# vfd_controller_cpu.net
KiCad netlist of a schematic drawn in EAGLE
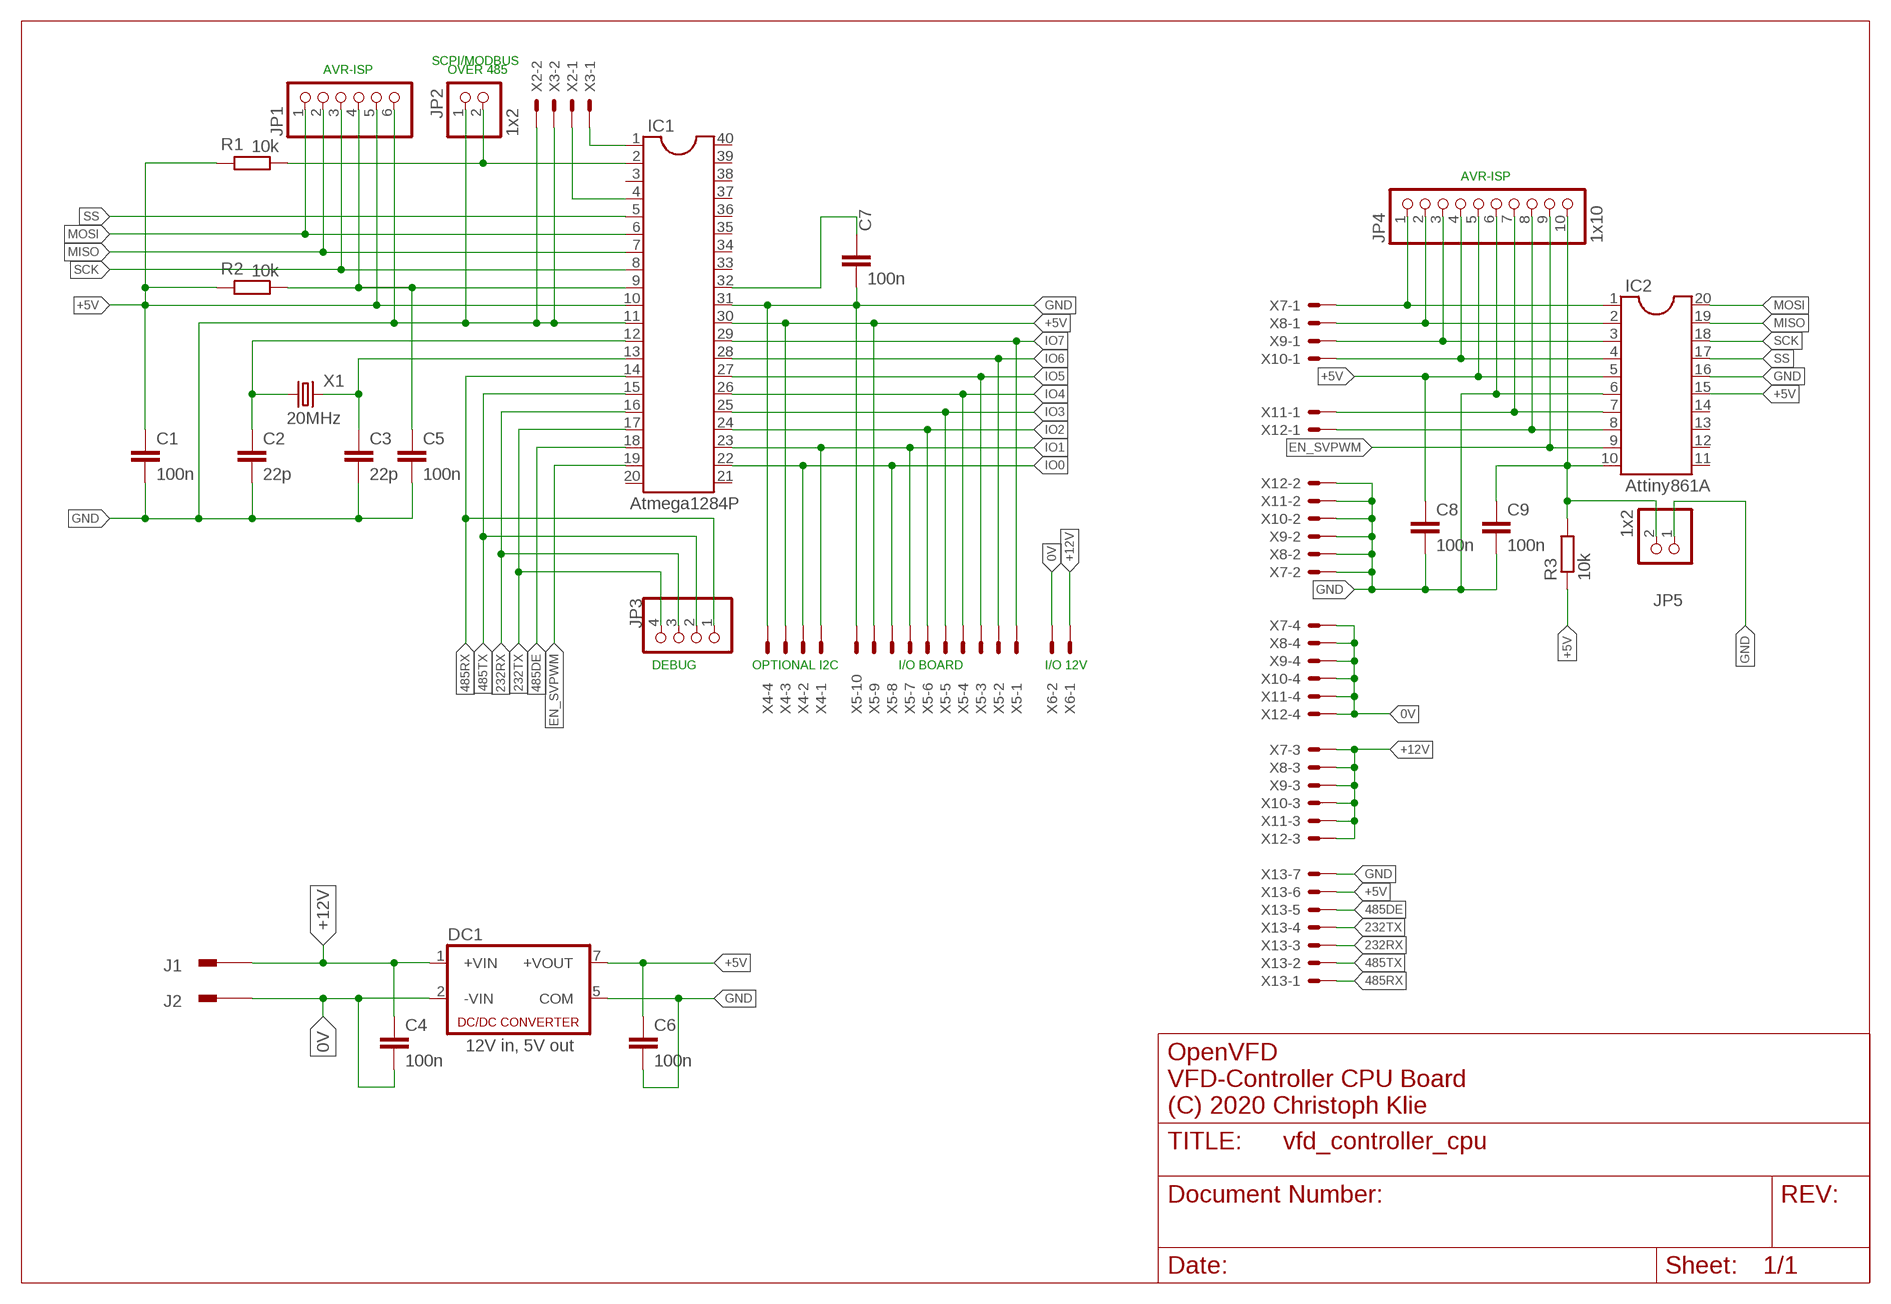
[diagram p0: schematic, sheet 1]

(export (version "E")
  (design (tool "Eeschema 10.0.6"))
  (components
    (comp (ref "C1")
      (value "100n")
      (footprint "eagle-import:C025-024X044")
      (libsource (lib "eagle-import") (part "C-EU025-024X044"))
    )
    (comp (ref "C2")
      (value "22p")
      (footprint "eagle-import:C025-024X044")
      (libsource (lib "eagle-import") (part "C-EU025-024X044"))
    )
    (comp (ref "C3")
      (value "22p")
      (footprint "eagle-import:C025-024X044")
      (libsource (lib "eagle-import") (part "C-EU025-024X044"))
    )
    (comp (ref "C4")
      (value "100n")
      (footprint "eagle-import:C025-024X044")
      (libsource (lib "eagle-import") (part "C-EU025-024X044"))
    )
    (comp (ref "C5")
      (value "100n")
      (footprint "eagle-import:C050-025X075")
      (libsource (lib "eagle-import") (part "C-EU050-025X075"))
    )
    (comp (ref "C6")
      (value "100n")
      (footprint "eagle-import:C050-025X075")
      (libsource (lib "eagle-import") (part "C-EU050-025X075"))
    )
    (comp (ref "C7")
      (value "100n")
      (footprint "eagle-import:C025-024X044")
      (libsource (lib "eagle-import") (part "C-EU025-024X044"))
    )
    (comp (ref "C8")
      (value "100n")
      (footprint "eagle-import:C025-024X044")
      (libsource (lib "eagle-import") (part "C-EU025-024X044"))
    )
    (comp (ref "C9")
      (value "100n")
      (footprint "eagle-import:C025-024X044")
      (libsource (lib "eagle-import") (part "C-EU025-024X044"))
    )
    (comp (ref "DC1")
      (value "12V in, 5V out")
      (footprint "eagle-import:MEV")
      (libsource (lib "eagle-import") (part "MEV"))
    )
    (comp (ref "IC1")
      (value "Atmega1284P")
      (footprint "eagle-import:DIL40")
      (libsource (lib "eagle-import") (part "DIL40"))
    )
    (comp (ref "IC2")
      (value "Attiny861A")
      (footprint "eagle-import:DIL20")
      (libsource (lib "eagle-import") (part "DIL20"))
    )
    (comp (ref "J1")
      (value "PIN2F061.200")
      (footprint "eagle-import:F061.200")
      (libsource (lib "eagle-import") (part "PIN2F061.200"))
    )
    (comp (ref "J2")
      (value "PIN2F061.200")
      (footprint "eagle-import:F061.200")
      (libsource (lib "eagle-import") (part "PIN2F061.200"))
    )
    (comp (ref "JP1")
      (value "1x6")
      (footprint "eagle-import:1X06")
      (libsource (lib "eagle-import") (part "PINHD-1X6"))
    )
    (comp (ref "JP2")
      (value "1x2")
      (footprint "eagle-import:1X02")
      (libsource (lib "eagle-import") (part "PINHD-1X2"))
    )
    (comp (ref "JP3")
      (value "1x4")
      (footprint "eagle-import:1X04")
      (libsource (lib "eagle-import") (part "PINHD-1X4"))
    )
    (comp (ref "JP4")
      (value "1x10")
      (footprint "eagle-import:1X10")
      (libsource (lib "eagle-import") (part "PINHD-1X10"))
    )
    (comp (ref "JP5")
      (value "1x2")
      (footprint "eagle-import:1X02")
      (libsource (lib "eagle-import") (part "PINHD-1X2"))
    )
    (comp (ref "R1")
      (value "10k")
      (footprint "eagle-import:0207_12")
      (libsource (lib "eagle-import") (part "R-EU_0207/12"))
    )
    (comp (ref "R2")
      (value "10k")
      (footprint "eagle-import:0204V")
      (libsource (lib "eagle-import") (part "R-EU_0204/2V"))
    )
    (comp (ref "R3")
      (value "10k")
      (footprint "eagle-import:0207_12")
      (libsource (lib "eagle-import") (part "R-EU_0207/12"))
    )
    (comp (ref "X1")
      (value "20MHz")
      (footprint "eagle-import:HC49")
      (libsource (lib "eagle-import") (part "CRYSTALS-NOGND-HC49"))
    )
    (comp (ref "X2")
      (value "JST-XH-02-PIN-LONG-PAD")
      (footprint "eagle-import:JST-XH-02-PACKAGE-LONG-PAD")
      (fields (field (name "R") "JST XH2P ST"))
      (libsource (lib "eagle-import") (part "JST-XH-02-PIN-LONG-PAD"))
    )
    (comp (ref "X3")
      (value "JST-XH-02-PIN-LONG-PAD")
      (footprint "eagle-import:JST-XH-02-PACKAGE-LONG-PAD")
      (fields (field (name "R") "JST XH2P ST"))
      (libsource (lib "eagle-import") (part "JST-XH-02-PIN-LONG-PAD"))
    )
    (comp (ref "X4")
      (value "JST-XH-04-PIN-LONG-PAD")
      (footprint "eagle-import:JST-XH-04-PACKAGE-LONG-PAD")
      (fields (field (name "R") "JST XH4P ST"))
      (libsource (lib "eagle-import") (part "JST-XH-04-PIN-LONG-PAD"))
    )
    (comp (ref "X5")
      (value "JST-XH-10-PIN-LONG-PAD")
      (footprint "eagle-import:JST-XH-10-PACKAGE-LONG-PAD")
      (fields (field (name "R") "JST XH10P ST"))
      (libsource (lib "eagle-import") (part "JST-XH-10-PIN-LONG-PAD"))
    )
    (comp (ref "X6")
      (value "JST-XH-02-PIN-LONG-PAD")
      (footprint "eagle-import:JST-XH-02-PACKAGE-LONG-PAD")
      (fields (field (name "R") "JST XH2P ST"))
      (libsource (lib "eagle-import") (part "JST-XH-02-PIN-LONG-PAD"))
    )
    (comp (ref "X7")
      (value "JST-XH-04-PIN-LONG-PAD")
      (footprint "eagle-import:JST-XH-04-PACKAGE-LONG-PAD")
      (fields (field (name "R") "JST XH4P ST"))
      (libsource (lib "eagle-import") (part "JST-XH-04-PIN-LONG-PAD"))
    )
    (comp (ref "X8")
      (value "JST-XH-04-PIN-LONG-PAD")
      (footprint "eagle-import:JST-XH-04-PACKAGE-LONG-PAD")
      (fields (field (name "R") "JST XH4P ST"))
      (libsource (lib "eagle-import") (part "JST-XH-04-PIN-LONG-PAD"))
    )
    (comp (ref "X9")
      (value "JST-XH-04-PIN-LONG-PAD")
      (footprint "eagle-import:JST-XH-04-PACKAGE-LONG-PAD")
      (fields (field (name "R") "JST XH4P ST"))
      (libsource (lib "eagle-import") (part "JST-XH-04-PIN-LONG-PAD"))
    )
    (comp (ref "X10")
      (value "JST-XH-04-PIN-LONG-PAD")
      (footprint "eagle-import:JST-XH-04-PACKAGE-LONG-PAD")
      (fields (field (name "R") "JST XH4P ST"))
      (libsource (lib "eagle-import") (part "JST-XH-04-PIN-LONG-PAD"))
    )
    (comp (ref "X11")
      (value "JST-XH-04-PIN-LONG-PAD")
      (footprint "eagle-import:JST-XH-04-PACKAGE-LONG-PAD")
      (fields (field (name "R") "JST XH4P ST"))
      (libsource (lib "eagle-import") (part "JST-XH-04-PIN-LONG-PAD"))
    )
    (comp (ref "X12")
      (value "JST-XH-04-PIN-LONG-PAD")
      (footprint "eagle-import:JST-XH-04-PACKAGE-LONG-PAD")
      (fields (field (name "R") "JST XH4P ST"))
      (libsource (lib "eagle-import") (part "JST-XH-04-PIN-LONG-PAD"))
    )
    (comp (ref "X13")
      (value "JST-XH-07-PIN-LONG-PAD")
      (footprint "eagle-import:JST-XH-07-PACKAGE-LONG-PAD")
      (fields (field (name "R") "JST XH7P ST"))
      (libsource (lib "eagle-import") (part "JST-XH-07-PIN-LONG-PAD"))
    )
  )
  (nets
    (net (code "1") (name "+5V") (class "Default")
      (node (ref "C1") (pin "1") (pinfunction "1_1") (pintype "passive"))
      (node (ref "C6") (pin "1") (pinfunction "1_1") (pintype "passive"))
      (node (ref "C8") (pin "1") (pinfunction "1_1") (pintype "passive"))
      (node (ref "DC1") (pin "7") (pinfunction "+VOUT_7") (pintype "passive"))
      (node (ref "IC1") (pin "10") (pinfunction "10_10") (pintype "passive"))
      (node (ref "IC1") (pin "30") (pinfunction "30_30") (pintype "passive"))
      (node (ref "IC2") (pin "15") (pinfunction "15_15") (pintype "passive"))
      (node (ref "IC2") (pin "5") (pinfunction "5_5") (pintype "passive"))
      (node (ref "JP1") (pin "5") (pinfunction "5_5") (pintype "passive"))
      (node (ref "JP4") (pin "5") (pinfunction "5_5") (pintype "passive"))
      (node (ref "R1") (pin "2") (pinfunction "2_2") (pintype "passive"))
      (node (ref "R2") (pin "2") (pinfunction "2_2") (pintype "passive"))
      (node (ref "R3") (pin "1") (pinfunction "1_1") (pintype "passive"))
      (node (ref "X13") (pin "6") (pinfunction "S_6") (pintype "passive"))
      (node (ref "X4") (pin "3") (pinfunction "S_3") (pintype "passive"))
      (node (ref "X5") (pin "9") (pinfunction "S_9") (pintype "passive"))
    )
    (net (code "2") (name "+12V") (class "Default")
      (node (ref "C4") (pin "1") (pinfunction "1_1") (pintype "passive"))
      (node (ref "DC1") (pin "1") (pinfunction "+VIN_1") (pintype "passive"))
      (node (ref "J1") (pin "1A") (pinfunction "1_1A") (pintype "passive"))
      (node (ref "J1") (pin "1B") (pinfunction "1_1B") (pintype "passive"))
      (node (ref "X10") (pin "3") (pinfunction "S_3") (pintype "passive"))
      (node (ref "X11") (pin "3") (pinfunction "S_3") (pintype "passive"))
      (node (ref "X12") (pin "3") (pinfunction "S_3") (pintype "passive"))
      (node (ref "X6") (pin "1") (pinfunction "S_1") (pintype "passive"))
      (node (ref "X7") (pin "3") (pinfunction "S_3") (pintype "passive"))
      (node (ref "X8") (pin "3") (pinfunction "S_3") (pintype "passive"))
      (node (ref "X9") (pin "3") (pinfunction "S_3") (pintype "passive"))
    )
    (net (code "3") (name "0V") (class "Default")
      (node (ref "C4") (pin "2") (pinfunction "2_2") (pintype "passive"))
      (node (ref "DC1") (pin "2") (pinfunction "-VIN_2") (pintype "passive"))
      (node (ref "J2") (pin "1A") (pinfunction "1_1A") (pintype "passive"))
      (node (ref "J2") (pin "1B") (pinfunction "1_1B") (pintype "passive"))
      (node (ref "X10") (pin "4") (pinfunction "S_4") (pintype "passive"))
      (node (ref "X11") (pin "4") (pinfunction "S_4") (pintype "passive"))
      (node (ref "X12") (pin "4") (pinfunction "S_4") (pintype "passive"))
      (node (ref "X6") (pin "2") (pinfunction "S_2") (pintype "passive"))
      (node (ref "X7") (pin "4") (pinfunction "S_4") (pintype "passive"))
      (node (ref "X8") (pin "4") (pinfunction "S_4") (pintype "passive"))
      (node (ref "X9") (pin "4") (pinfunction "S_4") (pintype "passive"))
    )
    (net (code "4") (name "232RX") (class "Default")
      (node (ref "IC1") (pin "16") (pinfunction "16_16") (pintype "passive"))
      (node (ref "JP3") (pin "3") (pinfunction "3_3") (pintype "passive"))
      (node (ref "X13") (pin "3") (pinfunction "S_3") (pintype "passive"))
    )
    (net (code "5") (name "232TX") (class "Default")
      (node (ref "IC1") (pin "17") (pinfunction "17_17") (pintype "passive"))
      (node (ref "JP3") (pin "4") (pinfunction "4_4") (pintype "passive"))
      (node (ref "X13") (pin "4") (pinfunction "S_4") (pintype "passive"))
    )
    (net (code "6") (name "485DE") (class "Default")
      (node (ref "IC1") (pin "18") (pinfunction "18_18") (pintype "passive"))
      (node (ref "X13") (pin "5") (pinfunction "S_5") (pintype "passive"))
    )
    (net (code "7") (name "485RX") (class "Default")
      (node (ref "IC1") (pin "14") (pinfunction "14_14") (pintype "passive"))
      (node (ref "JP3") (pin "1") (pinfunction "1_1") (pintype "passive"))
      (node (ref "X13") (pin "1") (pinfunction "S_1") (pintype "passive"))
    )
    (net (code "8") (name "485TX") (class "Default")
      (node (ref "IC1") (pin "15") (pinfunction "15_15") (pintype "passive"))
      (node (ref "JP3") (pin "2") (pinfunction "2_2") (pintype "passive"))
      (node (ref "X13") (pin "2") (pinfunction "S_2") (pintype "passive"))
    )
    (net (code "9") (name "EN_SVPWM") (class "Default")
      (node (ref "IC1") (pin "19") (pinfunction "19_19") (pintype "passive"))
      (node (ref "IC2") (pin "9") (pinfunction "9_9") (pintype "passive"))
      (node (ref "JP4") (pin "9") (pinfunction "9_9") (pintype "passive"))
    )
    (net (code "10") (name "GND") (class "Default")
      (node (ref "C1") (pin "2") (pinfunction "2_2") (pintype "passive"))
      (node (ref "C2") (pin "2") (pinfunction "2_2") (pintype "passive"))
      (node (ref "C3") (pin "2") (pinfunction "2_2") (pintype "passive"))
      (node (ref "C5") (pin "2") (pinfunction "2_2") (pintype "passive"))
      (node (ref "C6") (pin "2") (pinfunction "2_2") (pintype "passive"))
      (node (ref "C7") (pin "2") (pinfunction "2_2") (pintype "passive"))
      (node (ref "C8") (pin "2") (pinfunction "2_2") (pintype "passive"))
      (node (ref "C9") (pin "2") (pinfunction "2_2") (pintype "passive"))
      (node (ref "DC1") (pin "5") (pinfunction "COM_5") (pintype "passive"))
      (node (ref "IC1") (pin "11") (pinfunction "11_11") (pintype "passive"))
      (node (ref "IC1") (pin "31") (pinfunction "31_31") (pintype "passive"))
      (node (ref "IC2") (pin "16") (pinfunction "16_16") (pintype "passive"))
      (node (ref "IC2") (pin "6") (pinfunction "6_6") (pintype "passive"))
      (node (ref "JP1") (pin "6") (pinfunction "6_6") (pintype "passive"))
      (node (ref "JP2") (pin "1") (pinfunction "1_1") (pintype "passive"))
      (node (ref "JP4") (pin "6") (pinfunction "6_6") (pintype "passive"))
      (node (ref "JP5") (pin "1") (pinfunction "1_1") (pintype "passive"))
      (node (ref "X10") (pin "2") (pinfunction "S_2") (pintype "passive"))
      (node (ref "X11") (pin "2") (pinfunction "S_2") (pintype "passive"))
      (node (ref "X12") (pin "2") (pinfunction "S_2") (pintype "passive"))
      (node (ref "X13") (pin "7") (pinfunction "S_7") (pintype "passive"))
      (node (ref "X2") (pin "2") (pinfunction "S_2") (pintype "passive"))
      (node (ref "X3") (pin "2") (pinfunction "S_2") (pintype "passive"))
      (node (ref "X4") (pin "4") (pinfunction "S_4") (pintype "passive"))
      (node (ref "X5") (pin "10") (pinfunction "S_10") (pintype "passive"))
      (node (ref "X7") (pin "2") (pinfunction "S_2") (pintype "passive"))
      (node (ref "X8") (pin "2") (pinfunction "S_2") (pintype "passive"))
      (node (ref "X9") (pin "2") (pinfunction "S_2") (pintype "passive"))
    )
    (net (code "11") (name "IO0") (class "Default")
      (node (ref "IC1") (pin "22") (pinfunction "22_22") (pintype "passive"))
      (node (ref "X4") (pin "2") (pinfunction "S_2") (pintype "passive"))
      (node (ref "X5") (pin "8") (pinfunction "S_8") (pintype "passive"))
    )
    (net (code "12") (name "IO1") (class "Default")
      (node (ref "IC1") (pin "23") (pinfunction "23_23") (pintype "passive"))
      (node (ref "X4") (pin "1") (pinfunction "S_1") (pintype "passive"))
      (node (ref "X5") (pin "7") (pinfunction "S_7") (pintype "passive"))
    )
    (net (code "13") (name "IO2") (class "Default")
      (node (ref "IC1") (pin "24") (pinfunction "24_24") (pintype "passive"))
      (node (ref "X5") (pin "6") (pinfunction "S_6") (pintype "passive"))
    )
    (net (code "14") (name "IO3") (class "Default")
      (node (ref "IC1") (pin "25") (pinfunction "25_25") (pintype "passive"))
      (node (ref "X5") (pin "5") (pinfunction "S_5") (pintype "passive"))
    )
    (net (code "15") (name "IO4") (class "Default")
      (node (ref "IC1") (pin "26") (pinfunction "26_26") (pintype "passive"))
      (node (ref "X5") (pin "4") (pinfunction "S_4") (pintype "passive"))
    )
    (net (code "16") (name "IO5") (class "Default")
      (node (ref "IC1") (pin "27") (pinfunction "27_27") (pintype "passive"))
      (node (ref "X5") (pin "3") (pinfunction "S_3") (pintype "passive"))
    )
    (net (code "17") (name "IO6") (class "Default")
      (node (ref "IC1") (pin "28") (pinfunction "28_28") (pintype "passive"))
      (node (ref "X5") (pin "2") (pinfunction "S_2") (pintype "passive"))
    )
    (net (code "18") (name "IO7") (class "Default")
      (node (ref "IC1") (pin "29") (pinfunction "29_29") (pintype "passive"))
      (node (ref "X5") (pin "1") (pinfunction "S_1") (pintype "passive"))
    )
    (net (code "19") (name "MISO") (class "Default")
      (node (ref "IC1") (pin "7") (pinfunction "7_7") (pintype "passive"))
      (node (ref "IC2") (pin "19") (pinfunction "19_19") (pintype "passive"))
      (node (ref "JP1") (pin "2") (pinfunction "2_2") (pintype "passive"))
    )
    (net (code "20") (name "MOSI") (class "Default")
      (node (ref "IC1") (pin "6") (pinfunction "6_6") (pintype "passive"))
      (node (ref "IC2") (pin "20") (pinfunction "20_20") (pintype "passive"))
      (node (ref "JP1") (pin "1") (pinfunction "1_1") (pintype "passive"))
    )
    (net (code "21") (name "Net-(C2-Pad1)") (class "Default")
      (node (ref "C2") (pin "1") (pinfunction "1_1") (pintype "passive"))
      (node (ref "IC1") (pin "12") (pinfunction "12_12") (pintype "passive"))
      (node (ref "X1") (pin "1") (pinfunction "1_1") (pintype "passive"))
    )
    (net (code "22") (name "Net-(C3-Pad1)") (class "Default")
      (node (ref "C3") (pin "1") (pinfunction "1_1") (pintype "passive"))
      (node (ref "IC1") (pin "13") (pinfunction "13_13") (pintype "passive"))
      (node (ref "X1") (pin "2") (pinfunction "2_2") (pintype "passive"))
    )
    (net (code "23") (name "Net-(C5-Pad1)") (class "Default")
      (node (ref "C5") (pin "1") (pinfunction "1_1") (pintype "passive"))
      (node (ref "IC1") (pin "9") (pinfunction "9_9") (pintype "passive"))
      (node (ref "JP1") (pin "4") (pinfunction "4_4") (pintype "passive"))
      (node (ref "R2") (pin "1") (pinfunction "1_1") (pintype "passive"))
    )
    (net (code "24") (name "Net-(C7-Pad1)") (class "Default")
      (node (ref "C7") (pin "1") (pinfunction "1_1") (pintype "passive"))
      (node (ref "IC1") (pin "32") (pinfunction "32_32") (pintype "passive"))
    )
    (net (code "25") (name "Net-(C9-Pad1)") (class "Default")
      (node (ref "C9") (pin "1") (pinfunction "1_1") (pintype "passive"))
      (node (ref "IC2") (pin "10") (pinfunction "10_10") (pintype "passive"))
      (node (ref "JP4") (pin "10") (pinfunction "10_10") (pintype "passive"))
      (node (ref "JP5") (pin "2") (pinfunction "2_2") (pintype "passive"))
      (node (ref "R3") (pin "2") (pinfunction "2_2") (pintype "passive"))
    )
    (net (code "26") (name "Net-(IC1-Pad2)") (class "Default")
      (node (ref "IC1") (pin "2") (pinfunction "2_2") (pintype "passive"))
      (node (ref "JP2") (pin "2") (pinfunction "2_2") (pintype "passive"))
      (node (ref "R1") (pin "1") (pinfunction "1_1") (pintype "passive"))
    )
    (net (code "27") (name "Net-(X2A-S)") (class "Default")
      (node (ref "IC1") (pin "4") (pinfunction "4_4") (pintype "passive"))
      (node (ref "X2") (pin "1") (pinfunction "S_1") (pintype "passive"))
    )
    (net (code "28") (name "Net-(X3A-S)") (class "Default")
      (node (ref "IC1") (pin "1") (pinfunction "1_1") (pintype "passive"))
      (node (ref "X3") (pin "1") (pinfunction "S_1") (pintype "passive"))
    )
    (net (code "29") (name "Net-(X7A-S)") (class "Default")
      (node (ref "IC2") (pin "1") (pinfunction "1_1") (pintype "passive"))
      (node (ref "JP4") (pin "1") (pinfunction "1_1") (pintype "passive"))
      (node (ref "X7") (pin "1") (pinfunction "S_1") (pintype "passive"))
    )
    (net (code "30") (name "Net-(X8A-S)") (class "Default")
      (node (ref "IC2") (pin "2") (pinfunction "2_2") (pintype "passive"))
      (node (ref "JP4") (pin "2") (pinfunction "2_2") (pintype "passive"))
      (node (ref "X8") (pin "1") (pinfunction "S_1") (pintype "passive"))
    )
    (net (code "31") (name "Net-(X9A-S)") (class "Default")
      (node (ref "IC2") (pin "3") (pinfunction "3_3") (pintype "passive"))
      (node (ref "JP4") (pin "3") (pinfunction "3_3") (pintype "passive"))
      (node (ref "X9") (pin "1") (pinfunction "S_1") (pintype "passive"))
    )
    (net (code "32") (name "Net-(X10A-S)") (class "Default")
      (node (ref "IC2") (pin "4") (pinfunction "4_4") (pintype "passive"))
      (node (ref "JP4") (pin "4") (pinfunction "4_4") (pintype "passive"))
      (node (ref "X10") (pin "1") (pinfunction "S_1") (pintype "passive"))
    )
    (net (code "33") (name "Net-(X11A-S)") (class "Default")
      (node (ref "IC2") (pin "7") (pinfunction "7_7") (pintype "passive"))
      (node (ref "JP4") (pin "7") (pinfunction "7_7") (pintype "passive"))
      (node (ref "X11") (pin "1") (pinfunction "S_1") (pintype "passive"))
    )
    (net (code "34") (name "Net-(X12A-S)") (class "Default")
      (node (ref "IC2") (pin "8") (pinfunction "8_8") (pintype "passive"))
      (node (ref "JP4") (pin "8") (pinfunction "8_8") (pintype "passive"))
      (node (ref "X12") (pin "1") (pinfunction "S_1") (pintype "passive"))
    )
    (net (code "35") (name "SCK") (class "Default")
      (node (ref "IC1") (pin "8") (pinfunction "8_8") (pintype "passive"))
      (node (ref "IC2") (pin "18") (pinfunction "18_18") (pintype "passive"))
      (node (ref "JP1") (pin "3") (pinfunction "3_3") (pintype "passive"))
    )
    (net (code "36") (name "SS") (class "Default")
      (node (ref "IC1") (pin "5") (pinfunction "5_5") (pintype "passive"))
      (node (ref "IC2") (pin "17") (pinfunction "17_17") (pintype "passive"))
    )
    (net (code "37") (name "unconnected-(IC1-Pad3)") (class "Default")
      (node (ref "IC1") (pin "3") (pinfunction "3_3") (pintype "passive"))
    )
    (net (code "38") (name "unconnected-(IC1-Pad20)") (class "Default")
      (node (ref "IC1") (pin "20") (pinfunction "20_20") (pintype "passive"))
    )
    (net (code "39") (name "unconnected-(IC1-Pad21)") (class "Default")
      (node (ref "IC1") (pin "21") (pinfunction "21_21") (pintype "passive"))
    )
    (net (code "40") (name "unconnected-(IC1-Pad33)") (class "Default")
      (node (ref "IC1") (pin "33") (pinfunction "33_33") (pintype "passive"))
    )
    (net (code "41") (name "unconnected-(IC1-Pad34)") (class "Default")
      (node (ref "IC1") (pin "34") (pinfunction "34_34") (pintype "passive"))
    )
    (net (code "42") (name "unconnected-(IC1-Pad35)") (class "Default")
      (node (ref "IC1") (pin "35") (pinfunction "35_35") (pintype "passive"))
    )
    (net (code "43") (name "unconnected-(IC1-Pad36)") (class "Default")
      (node (ref "IC1") (pin "36") (pinfunction "36_36") (pintype "passive"))
    )
    (net (code "44") (name "unconnected-(IC1-Pad37)") (class "Default")
      (node (ref "IC1") (pin "37") (pinfunction "37_37") (pintype "passive"))
    )
    (net (code "45") (name "unconnected-(IC1-Pad38)") (class "Default")
      (node (ref "IC1") (pin "38") (pinfunction "38_38") (pintype "passive"))
    )
    (net (code "46") (name "unconnected-(IC1-Pad39)") (class "Default")
      (node (ref "IC1") (pin "39") (pinfunction "39_39") (pintype "passive"))
    )
    (net (code "47") (name "unconnected-(IC1-Pad40)") (class "Default")
      (node (ref "IC1") (pin "40") (pinfunction "40_40") (pintype "passive"))
    )
    (net (code "48") (name "unconnected-(IC2-Pad11)") (class "Default")
      (node (ref "IC2") (pin "11") (pinfunction "11_11") (pintype "passive"))
    )
    (net (code "49") (name "unconnected-(IC2-Pad12)") (class "Default")
      (node (ref "IC2") (pin "12") (pinfunction "12_12") (pintype "passive"))
    )
    (net (code "50") (name "unconnected-(IC2-Pad13)") (class "Default")
      (node (ref "IC2") (pin "13") (pinfunction "13_13") (pintype "passive"))
    )
    (net (code "51") (name "unconnected-(IC2-Pad14)") (class "Default")
      (node (ref "IC2") (pin "14") (pinfunction "14_14") (pintype "passive"))
    )
  )
)
